# rx.net
KiCad netlist of a schematic drawn in EAGLE
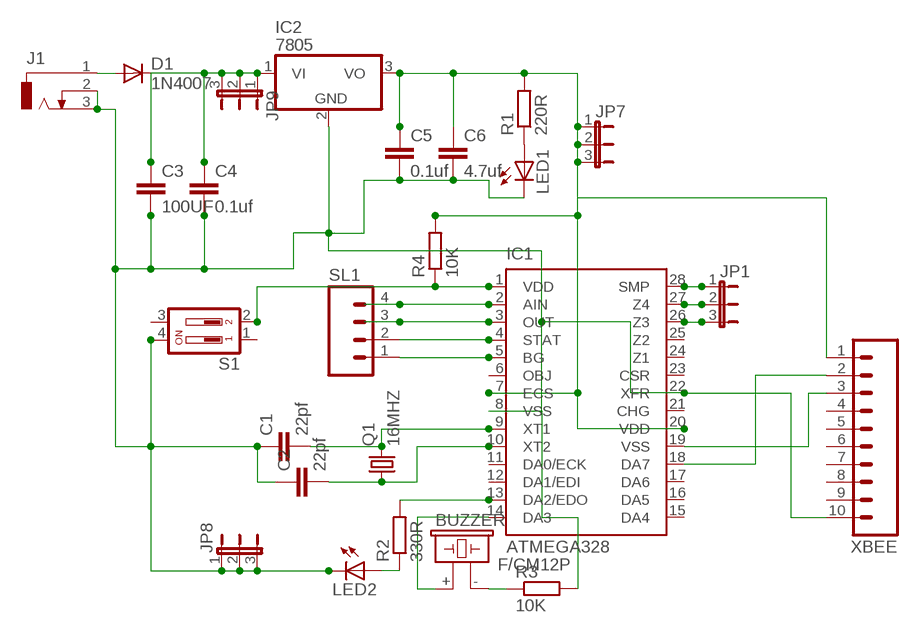
[diagram p0: schematic, sheet 1]

(export (version "E")
  (design (tool "Eeschema 10.0.6"))
  (components
    (comp (ref "BUZZER")
      (value "F/CM12P")
      (footprint "eagle-import:F_CM12P")
      (libsource (lib "eagle-import") (part "F/CM12P"))
    )
    (comp (ref "C1")
      (value "22pf")
      (footprint "eagle-import:C2.5-2")
      (libsource (lib "eagle-import") (part "C2.5/2"))
    )
    (comp (ref "C2")
      (value "22pf")
      (footprint "eagle-import:C2.5-2")
      (libsource (lib "eagle-import") (part "C2.5/2"))
    )
    (comp (ref "C3")
      (value "100UF")
      (footprint "eagle-import:C2.5-2")
      (libsource (lib "eagle-import") (part "C2.5/2"))
    )
    (comp (ref "C4")
      (value "0.1uf")
      (footprint "eagle-import:C2.5-2")
      (libsource (lib "eagle-import") (part "C2.5/2"))
    )
    (comp (ref "C5")
      (value "0.1uf")
      (footprint "eagle-import:C2.5-2")
      (libsource (lib "eagle-import") (part "C2.5/2"))
    )
    (comp (ref "C6")
      (value "4.7uf")
      (footprint "eagle-import:C2.5-2")
      (libsource (lib "eagle-import") (part "C2.5/2"))
    )
    (comp (ref "D1")
      (value "1N4007")
      (footprint "eagle-import:DO41-10")
      (libsource (lib "eagle-import") (part "1N4004"))
    )
    (comp (ref "IC1")
      (value "ATMEGA328")
      (footprint "eagle-import:DIL28-3")
      (libsource (lib "eagle-import") (part "QT9701BD"))
    )
    (comp (ref "IC2")
      (value "7805")
      (footprint "eagle-import:TO220V")
      (libsource (lib "eagle-import") (part "78TV6"))
    )
    (comp (ref "J1")
      (value "DCJ0303")
      (footprint "eagle-import:DCJ0303")
      (libsource (lib "eagle-import") (part "DCJ0303"))
    )
    (comp (ref "JP1")
      (value "JP2E")
      (footprint "eagle-import:JP2")
      (libsource (lib "eagle-import") (part "JP2E"))
    )
    (comp (ref "JP7")
      (value "JP2E")
      (footprint "eagle-import:JP2")
      (libsource (lib "eagle-import") (part "JP2E"))
    )
    (comp (ref "JP8")
      (value "JP2E")
      (footprint "eagle-import:JP2")
      (libsource (lib "eagle-import") (part "JP2E"))
    )
    (comp (ref "JP9")
      (value "JP2E")
      (footprint "eagle-import:JP2")
      (libsource (lib "eagle-import") (part "JP2E"))
    )
    (comp (ref "LED1")
      (value "LED3MM")
      (footprint "eagle-import:LED3MM")
      (libsource (lib "eagle-import") (part "LED3MM"))
    )
    (comp (ref "LED2")
      (value "LED3MM")
      (footprint "eagle-import:LED3MM")
      (libsource (lib "eagle-import") (part "LED3MM"))
    )
    (comp (ref "Q1")
      (value "16MHZ")
      (footprint "eagle-import:HC49_S")
      (libsource (lib "eagle-import") (part "CRYSTALHC49S"))
    )
    (comp (ref "R1")
      (value "220R")
      (footprint "eagle-import:0207_10")
      (libsource (lib "eagle-import") (part "R-EU_0207/10"))
    )
    (comp (ref "R2")
      (value "330R")
      (footprint "eagle-import:0207_10")
      (libsource (lib "eagle-import") (part "R-EU_0207/10"))
    )
    (comp (ref "R3")
      (value "10K")
      (footprint "eagle-import:0207_10")
      (libsource (lib "eagle-import") (part "R-EU_0207/10"))
    )
    (comp (ref "R4")
      (value "10K")
      (footprint "eagle-import:0207_10")
      (libsource (lib "eagle-import") (part "R-EU_0207/10"))
    )
    (comp (ref "S1")
      (value "DP02")
      (footprint "eagle-import:DP-02")
      (fields (field (name "MPN") "MCDP02"))
      (libsource (lib "eagle-import") (part "DP02"))
    )
    (comp (ref "SL1")
      (value "M04")
      (footprint "eagle-import:04P")
      (libsource (lib "eagle-import") (part "M04"))
    )
    (comp (ref "XBEE")
      (value "M10")
      (footprint "eagle-import:10P")
      (libsource (lib "eagle-import") (part "M10"))
    )
  )
  (nets
    (net (code "1") (name "Net-(BUZZER-1)") (class "Default")
      (node (ref "BUZZER") (pin "+") (pinfunction "1_+") (pintype "passive"))
      (node (ref "IC1") (pin "14") (pinfunction "DA3_14") (pintype "output"))
    )
    (net (code "2") (name "Net-(BUZZER-2)") (class "Default")
      (node (ref "BUZZER") (pin "-") (pinfunction "2_-") (pintype "passive"))
      (node (ref "R3") (pin "1") (pinfunction "1_1") (pintype "passive"))
    )
    (net (code "3") (name "Net-(D1-PadA)") (class "Default")
      (node (ref "D1") (pin "A") (pinfunction "A_A") (pintype "passive"))
      (node (ref "J1") (pin "1") (pinfunction "1_1") (pintype "passive"))
    )
    (net (code "4") (name "Net-(IC1-AIN)") (class "Default")
      (node (ref "IC1") (pin "2") (pinfunction "AIN_2") (pintype "input"))
      (node (ref "SL1") (pin "4") (pinfunction "4_4") (pintype "passive"))
    )
    (net (code "5") (name "Net-(IC1-BG)") (class "Default")
      (node (ref "IC1") (pin "5") (pinfunction "BG_5") (pintype "input"))
      (node (ref "SL1") (pin "1") (pinfunction "1_1") (pintype "passive"))
    )
    (net (code "6") (name "Net-(IC1-DA2{slash}EDO)") (class "Default")
      (node (ref "IC1") (pin "13") (pinfunction "DA2/EDO_13") (pintype "output"))
      (node (ref "R2") (pin "2") (pinfunction "2_2") (pintype "passive"))
    )
    (net (code "7") (name "Net-(IC1-DA7)") (class "Default")
      (node (ref "IC1") (pin "18") (pinfunction "DA7_18") (pintype "output"))
      (node (ref "XBEE") (pin "2") (pinfunction "2_2") (pintype "passive"))
    )
    (net (code "8") (name "Net-(IC1-ECS)") (class "Default")
      (node (ref "C5") (pin "1") (pinfunction "1_1") (pintype "passive"))
      (node (ref "C6") (pin "1") (pinfunction "1_1") (pintype "passive"))
      (node (ref "IC1") (pin "20") (pinfunction "VDD_20") (pintype "input"))
      (node (ref "IC1") (pin "7") (pinfunction "ECS_7") (pintype "output"))
      (node (ref "IC2") (pin "3") (pinfunction "VO_3") (pintype "passive"))
      (node (ref "JP7") (pin "1") (pinfunction "1_1") (pintype "passive"))
      (node (ref "JP7") (pin "2") (pinfunction "2_2") (pintype "passive"))
      (node (ref "JP7") (pin "3") (pinfunction "3_3") (pintype "passive"))
      (node (ref "R1") (pin "2") (pinfunction "2_2") (pintype "passive"))
      (node (ref "R4") (pin "2") (pinfunction "2_2") (pintype "passive"))
      (node (ref "XBEE") (pin "1") (pinfunction "1_1") (pintype "passive"))
    )
    (net (code "9") (name "Net-(IC1-OUT)") (class "Default")
      (node (ref "IC1") (pin "3") (pinfunction "OUT_3") (pintype "output"))
      (node (ref "SL1") (pin "3") (pinfunction "3_3") (pintype "passive"))
    )
    (net (code "10") (name "Net-(IC1-SMP)") (class "Default")
      (node (ref "IC1") (pin "28") (pinfunction "SMP_28") (pintype "output"))
      (node (ref "JP1") (pin "1") (pinfunction "1_1") (pintype "passive"))
    )
    (net (code "11") (name "Net-(IC1-STAT)") (class "Default")
      (node (ref "IC1") (pin "4") (pinfunction "STAT_4") (pintype "output"))
      (node (ref "SL1") (pin "2") (pinfunction "2_2") (pintype "passive"))
    )
    (net (code "12") (name "Net-(IC1-VDD-Pad1)") (class "Default")
      (node (ref "IC1") (pin "1") (pinfunction "VDD_1") (pintype "input"))
      (node (ref "R4") (pin "1") (pinfunction "1_1") (pintype "passive"))
      (node (ref "S1") (pin "2") (pinfunction "2_2") (pintype "passive"))
    )
    (net (code "13") (name "Net-(IC1-VSS-Pad19)") (class "Default")
      (node (ref "IC1") (pin "19") (pinfunction "VSS_19") (pintype "input"))
      (node (ref "XBEE") (pin "3") (pinfunction "3_3") (pintype "passive"))
    )
    (net (code "14") (name "Net-(IC1-XFR)") (class "Default")
      (node (ref "C1") (pin "1") (pinfunction "1_1") (pintype "passive"))
      (node (ref "C2") (pin "1") (pinfunction "1_1") (pintype "passive"))
      (node (ref "C3") (pin "2") (pinfunction "2_2") (pintype "passive"))
      (node (ref "C4") (pin "2") (pinfunction "2_2") (pintype "passive"))
      (node (ref "C5") (pin "2") (pinfunction "2_2") (pintype "passive"))
      (node (ref "C6") (pin "2") (pinfunction "2_2") (pintype "passive"))
      (node (ref "IC1") (pin "22") (pinfunction "XFR_22") (pintype "output"))
      (node (ref "IC1") (pin "8") (pinfunction "VSS_8") (pintype "input"))
      (node (ref "IC2") (pin "2") (pinfunction "GND_2") (pintype "passive"))
      (node (ref "J1") (pin "2") (pinfunction "2_2") (pintype "passive"))
      (node (ref "J1") (pin "3") (pinfunction "3_3") (pintype "passive"))
      (node (ref "JP8") (pin "1") (pinfunction "1_1") (pintype "passive"))
      (node (ref "JP8") (pin "2") (pinfunction "2_2") (pintype "passive"))
      (node (ref "JP8") (pin "3") (pinfunction "3_3") (pintype "passive"))
      (node (ref "LED1") (pin "K") (pinfunction "C_K") (pintype "passive"))
      (node (ref "LED2") (pin "K") (pinfunction "C_K") (pintype "passive"))
      (node (ref "R3") (pin "2") (pinfunction "2_2") (pintype "passive"))
      (node (ref "S1") (pin "4") (pinfunction "4_4") (pintype "passive"))
      (node (ref "XBEE") (pin "10") (pinfunction "10_10") (pintype "passive"))
    )
    (net (code "15") (name "Net-(IC1-XT1)") (class "Default")
      (node (ref "C1") (pin "2") (pinfunction "2_2") (pintype "passive"))
      (node (ref "IC1") (pin "9") (pinfunction "XT1_9") (pintype "input"))
      (node (ref "Q1") (pin "2") (pinfunction "2_2") (pintype "passive"))
    )
    (net (code "16") (name "Net-(IC1-XT2)") (class "Default")
      (node (ref "C2") (pin "2") (pinfunction "2_2") (pintype "passive"))
      (node (ref "IC1") (pin "10") (pinfunction "XT2_10") (pintype "output"))
      (node (ref "Q1") (pin "1") (pinfunction "1_1") (pintype "passive"))
    )
    (net (code "17") (name "Net-(IC1-Z3)") (class "Default")
      (node (ref "IC1") (pin "26") (pinfunction "Z3_26") (pintype "output"))
      (node (ref "JP1") (pin "3") (pinfunction "3_3") (pintype "passive"))
    )
    (net (code "18") (name "Net-(IC1-Z4)") (class "Default")
      (node (ref "IC1") (pin "27") (pinfunction "Z4_27") (pintype "output"))
      (node (ref "JP1") (pin "2") (pinfunction "2_2") (pintype "passive"))
    )
    (net (code "19") (name "Net-(IC2-VI)") (class "Default")
      (node (ref "C3") (pin "1") (pinfunction "1_1") (pintype "passive"))
      (node (ref "C4") (pin "1") (pinfunction "1_1") (pintype "passive"))
      (node (ref "D1") (pin "C") (pinfunction "C_C") (pintype "passive"))
      (node (ref "IC2") (pin "1") (pinfunction "VI_1") (pintype "input"))
      (node (ref "JP9") (pin "1") (pinfunction "1_1") (pintype "passive"))
      (node (ref "JP9") (pin "2") (pinfunction "2_2") (pintype "passive"))
      (node (ref "JP9") (pin "3") (pinfunction "3_3") (pintype "passive"))
    )
    (net (code "20") (name "Net-(LED1-PadA)") (class "Default")
      (node (ref "LED1") (pin "A") (pinfunction "A_A") (pintype "passive"))
      (node (ref "R1") (pin "1") (pinfunction "1_1") (pintype "passive"))
    )
    (net (code "21") (name "Net-(LED2-PadA)") (class "Default")
      (node (ref "LED2") (pin "A") (pinfunction "A_A") (pintype "passive"))
      (node (ref "R2") (pin "1") (pinfunction "1_1") (pintype "passive"))
    )
    (net (code "22") (name "unconnected-(IC1-CHG-Pad21)") (class "Default")
      (node (ref "IC1") (pin "21") (pinfunction "CHG_21") (pintype "output"))
    )
    (net (code "23") (name "unconnected-(IC1-CSR-Pad23)") (class "Default")
      (node (ref "IC1") (pin "23") (pinfunction "CSR_23") (pintype "output"))
    )
    (net (code "24") (name "unconnected-(IC1-DA0{slash}ECK-Pad11)") (class "Default")
      (node (ref "IC1") (pin "11") (pinfunction "DA0/ECK_11") (pintype "output"))
    )
    (net (code "25") (name "unconnected-(IC1-DA1{slash}EDI-Pad12)") (class "Default")
      (node (ref "IC1") (pin "12") (pinfunction "DA1/EDI_12") (pintype "output"))
    )
    (net (code "26") (name "unconnected-(IC1-DA4-Pad15)") (class "Default")
      (node (ref "IC1") (pin "15") (pinfunction "DA4_15") (pintype "output"))
    )
    (net (code "27") (name "unconnected-(IC1-DA5-Pad16)") (class "Default")
      (node (ref "IC1") (pin "16") (pinfunction "DA5_16") (pintype "output"))
    )
    (net (code "28") (name "unconnected-(IC1-DA6-Pad17)") (class "Default")
      (node (ref "IC1") (pin "17") (pinfunction "DA6_17") (pintype "output"))
    )
    (net (code "29") (name "unconnected-(IC1-OBJ-Pad6)") (class "Default")
      (node (ref "IC1") (pin "6") (pinfunction "OBJ_6") (pintype "input"))
    )
    (net (code "30") (name "unconnected-(IC1-Z1-Pad24)") (class "Default")
      (node (ref "IC1") (pin "24") (pinfunction "Z1_24") (pintype "output"))
    )
    (net (code "31") (name "unconnected-(IC1-Z2-Pad25)") (class "Default")
      (node (ref "IC1") (pin "25") (pinfunction "Z2_25") (pintype "output"))
    )
    (net (code "32") (name "unconnected-(S1-Pad1)") (class "Default")
      (node (ref "S1") (pin "1") (pinfunction "1_1") (pintype "passive"))
    )
    (net (code "33") (name "unconnected-(S1-Pad3)") (class "Default")
      (node (ref "S1") (pin "3") (pinfunction "3_3") (pintype "passive"))
    )
    (net (code "34") (name "unconnected-(XBEE-Pad4)") (class "Default")
      (node (ref "XBEE") (pin "4") (pinfunction "4_4") (pintype "passive"))
    )
    (net (code "35") (name "unconnected-(XBEE-Pad5)") (class "Default")
      (node (ref "XBEE") (pin "5") (pinfunction "5_5") (pintype "passive"))
    )
    (net (code "36") (name "unconnected-(XBEE-Pad6)") (class "Default")
      (node (ref "XBEE") (pin "6") (pinfunction "6_6") (pintype "passive"))
    )
    (net (code "37") (name "unconnected-(XBEE-Pad7)") (class "Default")
      (node (ref "XBEE") (pin "7") (pinfunction "7_7") (pintype "passive"))
    )
    (net (code "38") (name "unconnected-(XBEE-Pad8)") (class "Default")
      (node (ref "XBEE") (pin "8") (pinfunction "8_8") (pintype "passive"))
    )
    (net (code "39") (name "unconnected-(XBEE-Pad9)") (class "Default")
      (node (ref "XBEE") (pin "9") (pinfunction "9_9") (pintype "passive"))
    )
  )
)
